# HEATER-SSR.net
KiCad netlist of a schematic drawn in Altium Designer
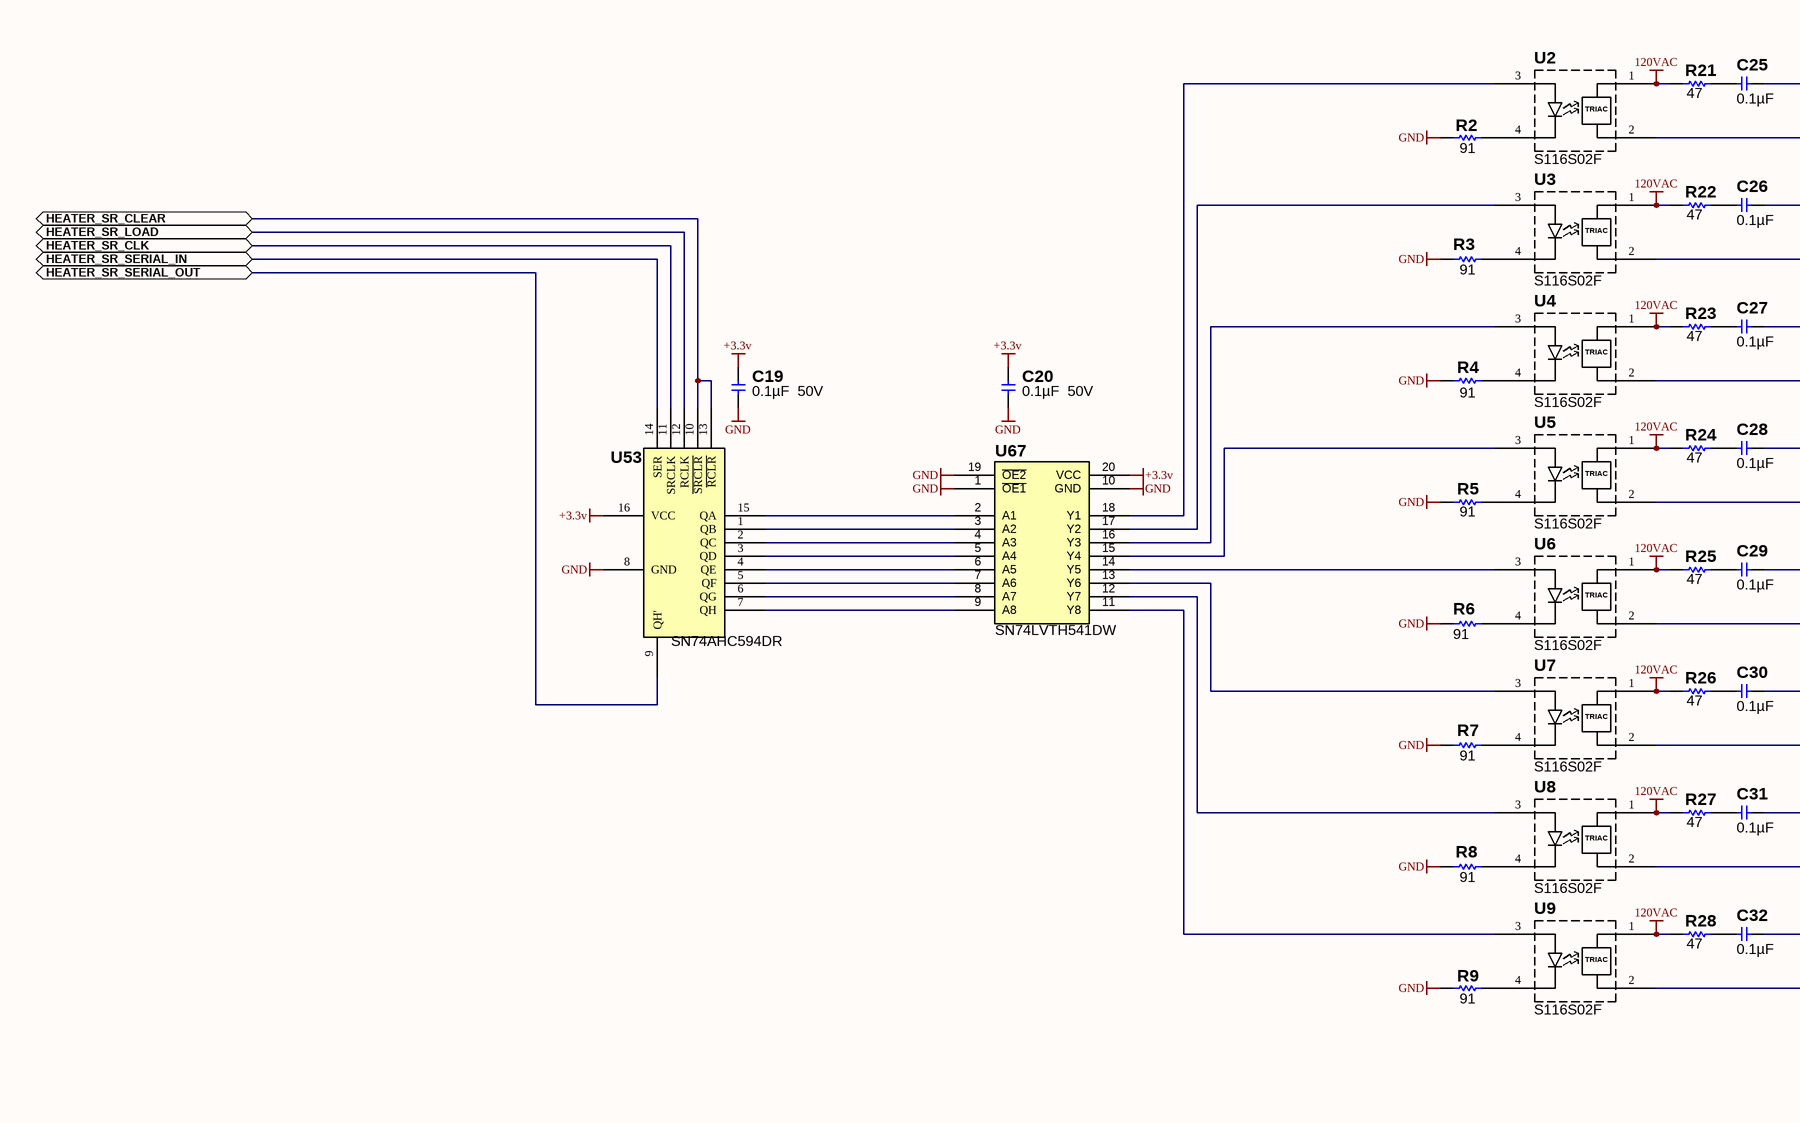
[diagram p0: HEATER-SSR.SchDoc, left]
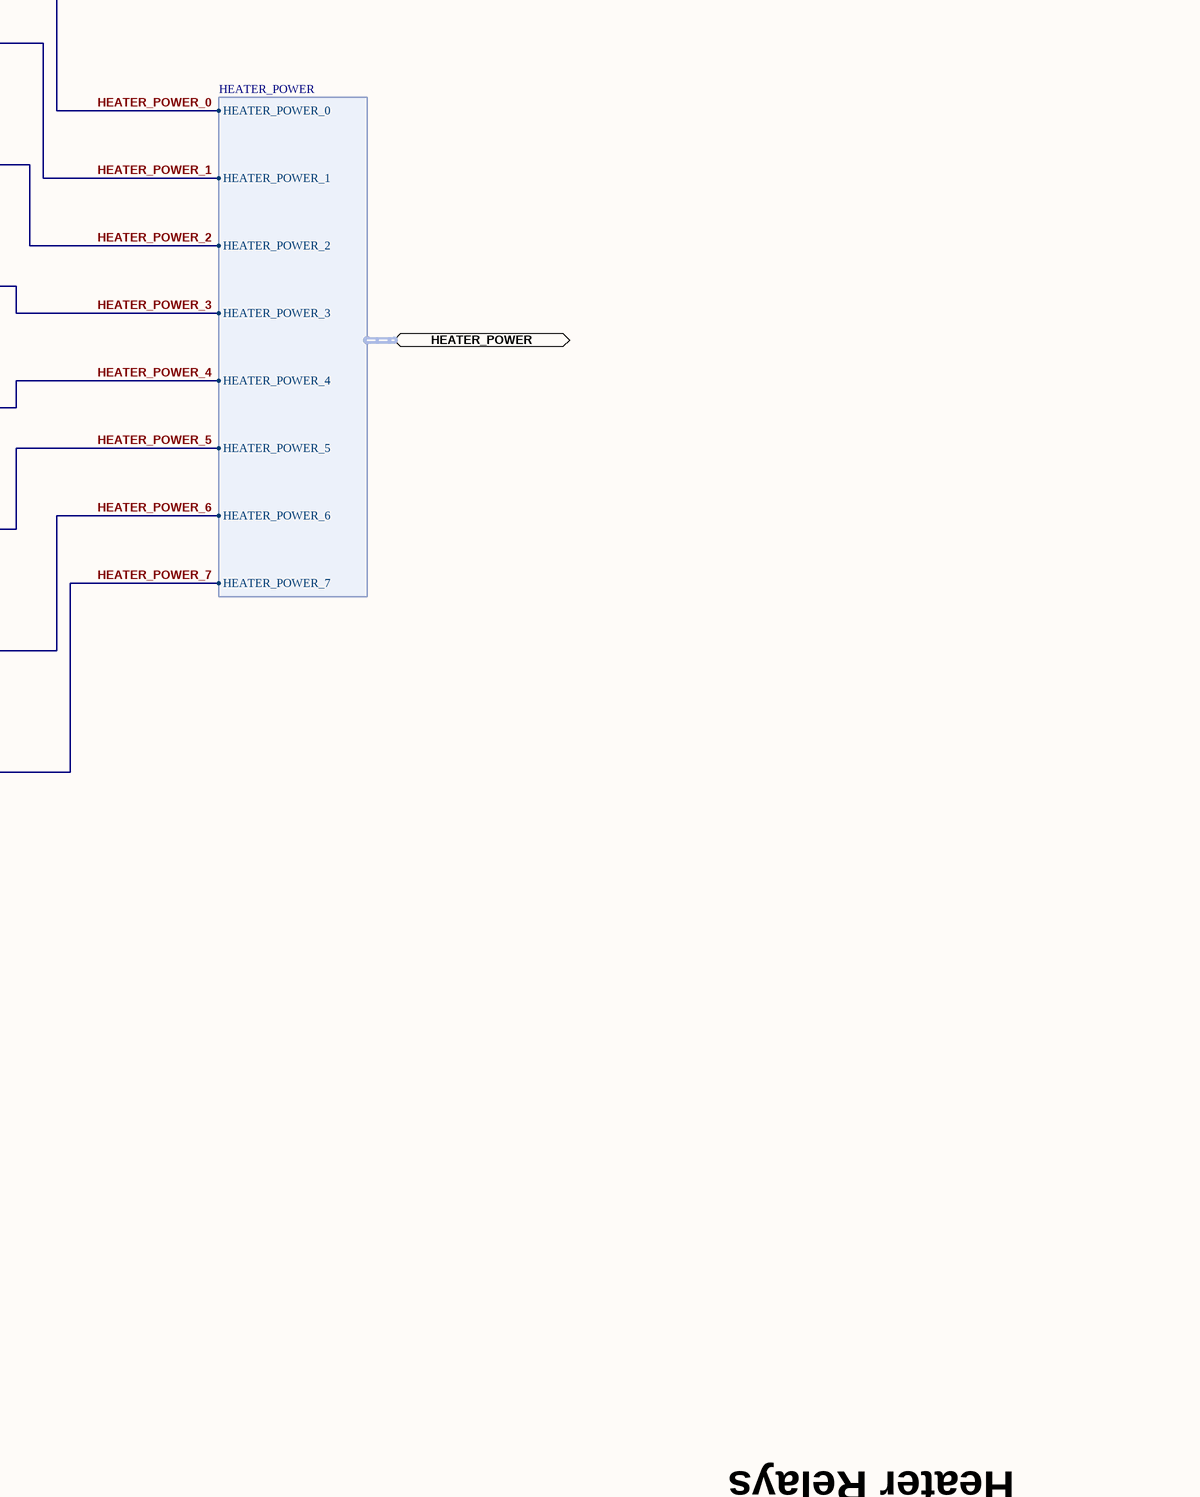
[diagram p1: HEATER-SSR.SchDoc, right]

(export (version "E")
  (design (tool "Eeschema 10.0.6"))
  (components
    (comp (ref "C19")
      (value "0.1µF  50V")
      (footprint "C0805_LD")
      (description "CAP CER 0.1UF 50V 10% X7R 0805")
      (fields
        (field (name "MANUFACTURER PART NUMBER") "GRM21BR71H104KA01L")
        (field (name "MANUFACTURER") "Murata Electronics North America")
      )
      (libsource (lib "Capacitors") (part "C_2P_NP"))
    )
    (comp (ref "C20")
      (value "0.1µF  50V")
      (footprint "C0805_LD")
      (description "CAP CER 0.1UF 50V 10% X7R 0805")
      (fields
        (field (name "MANUFACTURER PART NUMBER") "GRM21BR71H104KA01L")
        (field (name "MANUFACTURER") "Murata Electronics North America")
      )
      (libsource (lib "Capacitors") (part "C_2P_NP"))
    )
    (comp (ref "C25")
      (value "0.1µF")
      (footprint "C1206_LD")
      (description "CAP CER 0.1UF 250V 10% X7R 1206")
      (fields
        (field (name "MANUFACTURER PART NUMBER") "GRM31CR72E104KW03L")
        (field (name "MANUFACTURER") "Murata Electronics North America")
      )
      (libsource (lib "Diodes") (part "C_2P_NP"))
    )
    (comp (ref "C26")
      (value "0.1µF")
      (footprint "C1206_LD")
      (description "CAP CER 0.1UF 250V 10% X7R 1206")
      (fields
        (field (name "MANUFACTURER PART NUMBER") "GRM31CR72E104KW03L")
        (field (name "MANUFACTURER") "Murata Electronics North America")
      )
      (libsource (lib "Diodes") (part "C_2P_NP"))
    )
    (comp (ref "C27")
      (value "0.1µF")
      (footprint "C1206_LD")
      (description "CAP CER 0.1UF 250V 10% X7R 1206")
      (fields
        (field (name "MANUFACTURER PART NUMBER") "GRM31CR72E104KW03L")
        (field (name "MANUFACTURER") "Murata Electronics North America")
      )
      (libsource (lib "Diodes") (part "C_2P_NP"))
    )
    (comp (ref "C28")
      (value "0.1µF")
      (footprint "C1206_LD")
      (description "CAP CER 0.1UF 250V 10% X7R 1206")
      (fields
        (field (name "MANUFACTURER PART NUMBER") "GRM31CR72E104KW03L")
        (field (name "MANUFACTURER") "Murata Electronics North America")
      )
      (libsource (lib "Diodes") (part "C_2P_NP"))
    )
    (comp (ref "C29")
      (value "0.1µF")
      (footprint "C1206_LD")
      (description "CAP CER 0.1UF 250V 10% X7R 1206")
      (fields
        (field (name "MANUFACTURER PART NUMBER") "GRM31CR72E104KW03L")
        (field (name "MANUFACTURER") "Murata Electronics North America")
      )
      (libsource (lib "Diodes") (part "C_2P_NP"))
    )
    (comp (ref "C30")
      (value "0.1µF")
      (footprint "C1206_LD")
      (description "CAP CER 0.1UF 250V 10% X7R 1206")
      (fields
        (field (name "MANUFACTURER PART NUMBER") "GRM31CR72E104KW03L")
        (field (name "MANUFACTURER") "Murata Electronics North America")
      )
      (libsource (lib "Diodes") (part "C_2P_NP"))
    )
    (comp (ref "C31")
      (value "0.1µF")
      (footprint "C1206_LD")
      (description "CAP CER 0.1UF 250V 10% X7R 1206")
      (fields
        (field (name "MANUFACTURER PART NUMBER") "GRM31CR72E104KW03L")
        (field (name "MANUFACTURER") "Murata Electronics North America")
      )
      (libsource (lib "Diodes") (part "C_2P_NP"))
    )
    (comp (ref "C32")
      (value "0.1µF")
      (footprint "C1206_LD")
      (description "CAP CER 0.1UF 250V 10% X7R 1206")
      (fields
        (field (name "MANUFACTURER PART NUMBER") "GRM31CR72E104KW03L")
        (field (name "MANUFACTURER") "Murata Electronics North America")
      )
      (libsource (lib "Diodes") (part "C_2P_NP"))
    )
    (comp (ref "R2")
      (value "91")
      (footprint "R0805_LD")
      (description "RES 91 OHM 1/8W 1% 0805 SMD")
      (fields
        (field (name "MANUFACTURER PART NUMBER") "ERJ-6ENF91R0V")
        (field (name "MANUFACTURER") "Panasonic Electronic Components")
      )
      (libsource (lib "Resistors") (part "R_2P"))
    )
    (comp (ref "R3")
      (value "91")
      (footprint "R0805_LD")
      (description "RES 91 OHM 1/8W 1% 0805 SMD")
      (fields
        (field (name "MANUFACTURER PART NUMBER") "ERJ-6ENF91R0V")
        (field (name "MANUFACTURER") "Panasonic Electronic Components")
      )
      (libsource (lib "Resistors") (part "R_2P"))
    )
    (comp (ref "R4")
      (value "91")
      (footprint "R0805_LD")
      (description "RES 91 OHM 1/8W 1% 0805 SMD")
      (fields
        (field (name "MANUFACTURER PART NUMBER") "ERJ-6ENF91R0V")
        (field (name "MANUFACTURER") "Panasonic Electronic Components")
      )
      (libsource (lib "Resistors") (part "R_2P"))
    )
    (comp (ref "R5")
      (value "91")
      (footprint "R0805_LD")
      (description "RES 91 OHM 1/8W 1% 0805 SMD")
      (fields
        (field (name "MANUFACTURER PART NUMBER") "ERJ-6ENF91R0V")
        (field (name "MANUFACTURER") "Panasonic Electronic Components")
      )
      (libsource (lib "Resistors") (part "R_2P"))
    )
    (comp (ref "R6")
      (value "91")
      (footprint "R0805_LD")
      (description "RES 91 OHM 1/8W 1% 0805 SMD")
      (fields
        (field (name "MANUFACTURER PART NUMBER") "ERJ-6ENF91R0V")
        (field (name "MANUFACTURER") "Panasonic Electronic Components")
      )
      (libsource (lib "Resistors") (part "R_2P"))
    )
    (comp (ref "R7")
      (value "91")
      (footprint "R0805_LD")
      (description "RES 91 OHM 1/8W 1% 0805 SMD")
      (fields
        (field (name "MANUFACTURER PART NUMBER") "ERJ-6ENF91R0V")
        (field (name "MANUFACTURER") "Panasonic Electronic Components")
      )
      (libsource (lib "Resistors") (part "R_2P"))
    )
    (comp (ref "R8")
      (value "91")
      (footprint "R0805_LD")
      (description "RES 91 OHM 1/8W 1% 0805 SMD")
      (fields
        (field (name "MANUFACTURER PART NUMBER") "ERJ-6ENF91R0V")
        (field (name "MANUFACTURER") "Panasonic Electronic Components")
      )
      (libsource (lib "Resistors") (part "R_2P"))
    )
    (comp (ref "R9")
      (value "91")
      (footprint "R0805_LD")
      (description "RES 91 OHM 1/8W 1% 0805 SMD")
      (fields
        (field (name "MANUFACTURER PART NUMBER") "ERJ-6ENF91R0V")
        (field (name "MANUFACTURER") "Panasonic Electronic Components")
      )
      (libsource (lib "Resistors") (part "R_2P"))
    )
    (comp (ref "R21")
      (value "47")
      (footprint "R1206_LD")
      (description "RES 47 OHM 1/4W 1% 1206 SMD")
      (fields
        (field (name "MANUFACTURER PART NUMBER") "ERJ-8ENF47R0V")
        (field (name "MANUFACTURER") "Panasonic Electronic Components")
      )
      (libsource (lib "Diodes") (part "R_2P"))
    )
    (comp (ref "R22")
      (value "47")
      (footprint "R1206_LD")
      (description "RES 47 OHM 1/4W 1% 1206 SMD")
      (fields
        (field (name "MANUFACTURER PART NUMBER") "ERJ-8ENF47R0V")
        (field (name "MANUFACTURER") "Panasonic Electronic Components")
      )
      (libsource (lib "Diodes") (part "R_2P"))
    )
    (comp (ref "R23")
      (value "47")
      (footprint "R1206_LD")
      (description "RES 47 OHM 1/4W 1% 1206 SMD")
      (fields
        (field (name "MANUFACTURER PART NUMBER") "ERJ-8ENF47R0V")
        (field (name "MANUFACTURER") "Panasonic Electronic Components")
      )
      (libsource (lib "Diodes") (part "R_2P"))
    )
    (comp (ref "R24")
      (value "47")
      (footprint "R1206_LD")
      (description "RES 47 OHM 1/4W 1% 1206 SMD")
      (fields
        (field (name "MANUFACTURER PART NUMBER") "ERJ-8ENF47R0V")
        (field (name "MANUFACTURER") "Panasonic Electronic Components")
      )
      (libsource (lib "Diodes") (part "R_2P"))
    )
    (comp (ref "R25")
      (value "47")
      (footprint "R1206_LD")
      (description "RES 47 OHM 1/4W 1% 1206 SMD")
      (fields
        (field (name "MANUFACTURER PART NUMBER") "ERJ-8ENF47R0V")
        (field (name "MANUFACTURER") "Panasonic Electronic Components")
      )
      (libsource (lib "Diodes") (part "R_2P"))
    )
    (comp (ref "R26")
      (value "47")
      (footprint "R1206_LD")
      (description "RES 47 OHM 1/4W 1% 1206 SMD")
      (fields
        (field (name "MANUFACTURER PART NUMBER") "ERJ-8ENF47R0V")
        (field (name "MANUFACTURER") "Panasonic Electronic Components")
      )
      (libsource (lib "Diodes") (part "R_2P"))
    )
    (comp (ref "R27")
      (value "47")
      (footprint "R1206_LD")
      (description "RES 47 OHM 1/4W 1% 1206 SMD")
      (fields
        (field (name "MANUFACTURER PART NUMBER") "ERJ-8ENF47R0V")
        (field (name "MANUFACTURER") "Panasonic Electronic Components")
      )
      (libsource (lib "Diodes") (part "R_2P"))
    )
    (comp (ref "R28")
      (value "47")
      (footprint "R1206_LD")
      (description "RES 47 OHM 1/4W 1% 1206 SMD")
      (fields
        (field (name "MANUFACTURER PART NUMBER") "ERJ-8ENF47R0V")
        (field (name "MANUFACTURER") "Panasonic Electronic Components")
      )
      (libsource (lib "Diodes") (part "R_2P"))
    )
    (comp (ref "U2")
      (value "S116S02F")
      (footprint "SHARP SIP-4 SSR")
      (description "Solid State Relays - PCB Mount 16A Zero Cross Type Triac output SSR")
      (fields (field (name "MANUFACTURER") "Sharp Microelectronics"))
      (libsource (lib "eIC") (part "S116S02F"))
    )
    (comp (ref "U3")
      (value "S116S02F")
      (footprint "SHARP SIP-4 SSR")
      (description "Solid State Relays - PCB Mount 16A Zero Cross Type Triac output SSR")
      (fields (field (name "MANUFACTURER") "Sharp Microelectronics"))
      (libsource (lib "eIC") (part "S116S02F"))
    )
    (comp (ref "U4")
      (value "S116S02F")
      (footprint "SHARP SIP-4 SSR")
      (description "Solid State Relays - PCB Mount 16A Zero Cross Type Triac output SSR")
      (fields (field (name "MANUFACTURER") "Sharp Microelectronics"))
      (libsource (lib "eIC") (part "S116S02F"))
    )
    (comp (ref "U5")
      (value "S116S02F")
      (footprint "SHARP SIP-4 SSR")
      (description "Solid State Relays - PCB Mount 16A Zero Cross Type Triac output SSR")
      (fields (field (name "MANUFACTURER") "Sharp Microelectronics"))
      (libsource (lib "eIC") (part "S116S02F"))
    )
    (comp (ref "U6")
      (value "S116S02F")
      (footprint "SHARP SIP-4 SSR")
      (description "Solid State Relays - PCB Mount 16A Zero Cross Type Triac output SSR")
      (fields (field (name "MANUFACTURER") "Sharp Microelectronics"))
      (libsource (lib "eIC") (part "S116S02F"))
    )
    (comp (ref "U7")
      (value "S116S02F")
      (footprint "SHARP SIP-4 SSR")
      (description "Solid State Relays - PCB Mount 16A Zero Cross Type Triac output SSR")
      (fields (field (name "MANUFACTURER") "Sharp Microelectronics"))
      (libsource (lib "eIC") (part "S116S02F"))
    )
    (comp (ref "U8")
      (value "S116S02F")
      (footprint "SHARP SIP-4 SSR")
      (description "Solid State Relays - PCB Mount 16A Zero Cross Type Triac output SSR")
      (fields (field (name "MANUFACTURER") "Sharp Microelectronics"))
      (libsource (lib "eIC") (part "S116S02F"))
    )
    (comp (ref "U9")
      (value "S116S02F")
      (footprint "SHARP SIP-4 SSR")
      (description "Solid State Relays - PCB Mount 16A Zero Cross Type Triac output SSR")
      (fields (field (name "MANUFACTURER") "Sharp Microelectronics"))
      (libsource (lib "eIC") (part "S116S02F"))
    )
    (comp (ref "U53")
      (value "SN74AHC594DR")
      (footprint "SOIC127P600X145-16L")
      (description "IC SHIFT REGISTER 8BIT 16-SOIC")
      (fields (field (name "MANUFACTURER") "Texas Instruments"))
      (libsource (lib "eIC") (part "SN74AHC594DR"))
    )
    (comp (ref "U67")
      (value "SN74LVTH541DW")
      (footprint "SOIC127P1030X265-20L")
      (description "IC BUFF/DVR TRI-ST 8BIT 20SOIC")
      (fields (field (name "MANUFACTURER") "Texas Instruments"))
      (libsource (lib "eIC") (part "SN74LVTH541DW"))
    )
  )
  (nets
    (net (code "2") (name "+3.3v") (class "Default")
      (node (ref "C19") (pin "2") (pinfunction "2_2") (pintype "passive"))
      (node (ref "C20") (pin "2") (pinfunction "2_2") (pintype "passive"))
      (node (ref "U53") (pin "16") (pinfunction "VCC_16") (pintype "passive"))
      (node (ref "U67") (pin "20") (pinfunction "VCC_20") (pintype "passive"))
    )
    (net (code "3") (name "/HEATER_POWER_0") (class "Default")
      (node (ref "C25") (pin "2") (pinfunction "2_2") (pintype "passive"))
      (node (ref "U2") (pin "2") (pinfunction "2_2") (pintype "passive"))
    )
    (net (code "4") (name "/HEATER_POWER_1") (class "Default")
      (node (ref "C26") (pin "2") (pinfunction "2_2") (pintype "passive"))
      (node (ref "U3") (pin "2") (pinfunction "2_2") (pintype "passive"))
    )
    (net (code "5") (name "/HEATER_POWER_2") (class "Default")
      (node (ref "C27") (pin "2") (pinfunction "2_2") (pintype "passive"))
      (node (ref "U4") (pin "2") (pinfunction "2_2") (pintype "passive"))
    )
    (net (code "6") (name "/HEATER_POWER_3") (class "Default")
      (node (ref "C28") (pin "2") (pinfunction "2_2") (pintype "passive"))
      (node (ref "U5") (pin "2") (pinfunction "2_2") (pintype "passive"))
    )
    (net (code "7") (name "/HEATER_POWER_4") (class "Default")
      (node (ref "C29") (pin "2") (pinfunction "2_2") (pintype "passive"))
      (node (ref "U6") (pin "2") (pinfunction "2_2") (pintype "passive"))
    )
    (net (code "8") (name "/HEATER_POWER_5") (class "Default")
      (node (ref "C30") (pin "2") (pinfunction "2_2") (pintype "passive"))
      (node (ref "U7") (pin "2") (pinfunction "2_2") (pintype "passive"))
    )
    (net (code "9") (name "/HEATER_POWER_6") (class "Default")
      (node (ref "C31") (pin "2") (pinfunction "2_2") (pintype "passive"))
      (node (ref "U8") (pin "2") (pinfunction "2_2") (pintype "passive"))
    )
    (net (code "10") (name "/HEATER_POWER_7") (class "Default")
      (node (ref "C32") (pin "2") (pinfunction "2_2") (pintype "passive"))
      (node (ref "U9") (pin "2") (pinfunction "2_2") (pintype "passive"))
    )
    (net (code "11") (name "/HEATER_SR_CLEAR") (class "Default")
      (node (ref "U53") (pin "10") (pinfunction "~{SRCLR}_10") (pintype "passive"))
      (node (ref "U53") (pin "13") (pinfunction "~{RCLR}_13") (pintype "passive"))
    )
    (net (code "12") (name "/HEATER_SR_CLK") (class "Default")
      (node (ref "U53") (pin "11") (pinfunction "SRCLK_11") (pintype "passive"))
    )
    (net (code "13") (name "/HEATER_SR_LOAD") (class "Default")
      (node (ref "U53") (pin "12") (pinfunction "RCLK_12") (pintype "passive"))
    )
    (net (code "14") (name "/HEATER_SR_SERIAL_IN") (class "Default")
      (node (ref "U53") (pin "14") (pinfunction "SER_14") (pintype "passive"))
    )
    (net (code "15") (name "/HEATER_SR_SERIAL_OUT") (class "Default")
      (node (ref "U53") (pin "9") (pinfunction "QH'_9") (pintype "passive"))
    )
    (net (code "17") (name "120VAC") (class "Default")
      (node (ref "R21") (pin "1") (pinfunction "1_1") (pintype "passive"))
      (node (ref "R22") (pin "1") (pinfunction "1_1") (pintype "passive"))
      (node (ref "R23") (pin "1") (pinfunction "1_1") (pintype "passive"))
      (node (ref "R24") (pin "1") (pinfunction "1_1") (pintype "passive"))
      (node (ref "R25") (pin "1") (pinfunction "1_1") (pintype "passive"))
      (node (ref "R26") (pin "1") (pinfunction "1_1") (pintype "passive"))
      (node (ref "R27") (pin "1") (pinfunction "1_1") (pintype "passive"))
      (node (ref "R28") (pin "1") (pinfunction "1_1") (pintype "passive"))
      (node (ref "U2") (pin "1") (pinfunction "1_1") (pintype "passive"))
      (node (ref "U3") (pin "1") (pinfunction "1_1") (pintype "passive"))
      (node (ref "U4") (pin "1") (pinfunction "1_1") (pintype "passive"))
      (node (ref "U5") (pin "1") (pinfunction "1_1") (pintype "passive"))
      (node (ref "U6") (pin "1") (pinfunction "1_1") (pintype "passive"))
      (node (ref "U7") (pin "1") (pinfunction "1_1") (pintype "passive"))
      (node (ref "U8") (pin "1") (pinfunction "1_1") (pintype "passive"))
      (node (ref "U9") (pin "1") (pinfunction "1_1") (pintype "passive"))
    )
    (net (code "18") (name "GND") (class "Default")
      (node (ref "C19") (pin "1") (pinfunction "1_1") (pintype "passive"))
      (node (ref "C20") (pin "1") (pinfunction "1_1") (pintype "passive"))
      (node (ref "R2") (pin "1") (pinfunction "1_1") (pintype "passive"))
      (node (ref "R3") (pin "1") (pinfunction "1_1") (pintype "passive"))
      (node (ref "R4") (pin "1") (pinfunction "1_1") (pintype "passive"))
      (node (ref "R5") (pin "1") (pinfunction "1_1") (pintype "passive"))
      (node (ref "R6") (pin "1") (pinfunction "1_1") (pintype "passive"))
      (node (ref "R7") (pin "1") (pinfunction "1_1") (pintype "passive"))
      (node (ref "R8") (pin "1") (pinfunction "1_1") (pintype "passive"))
      (node (ref "R9") (pin "1") (pinfunction "1_1") (pintype "passive"))
      (node (ref "U53") (pin "8") (pinfunction "GND_8") (pintype "passive"))
      (node (ref "U67") (pin "1") (pinfunction "~{OE1}_1") (pintype "passive"))
      (node (ref "U67") (pin "10") (pinfunction "GND_10") (pintype "passive"))
      (node (ref "U67") (pin "19") (pinfunction "~{OE2}_19") (pintype "passive"))
    )
    (net (code "19") (name "Net-(C25-Pad1)") (class "Default")
      (node (ref "C25") (pin "1") (pinfunction "1_1") (pintype "passive"))
      (node (ref "R21") (pin "2") (pinfunction "2_2") (pintype "passive"))
    )
    (net (code "20") (name "Net-(C26-Pad1)") (class "Default")
      (node (ref "C26") (pin "1") (pinfunction "1_1") (pintype "passive"))
      (node (ref "R22") (pin "2") (pinfunction "2_2") (pintype "passive"))
    )
    (net (code "21") (name "Net-(C27-Pad1)") (class "Default")
      (node (ref "C27") (pin "1") (pinfunction "1_1") (pintype "passive"))
      (node (ref "R23") (pin "2") (pinfunction "2_2") (pintype "passive"))
    )
    (net (code "22") (name "Net-(C28-Pad1)") (class "Default")
      (node (ref "C28") (pin "1") (pinfunction "1_1") (pintype "passive"))
      (node (ref "R24") (pin "2") (pinfunction "2_2") (pintype "passive"))
    )
    (net (code "23") (name "Net-(C29-Pad1)") (class "Default")
      (node (ref "C29") (pin "1") (pinfunction "1_1") (pintype "passive"))
      (node (ref "R25") (pin "2") (pinfunction "2_2") (pintype "passive"))
    )
    (net (code "24") (name "Net-(C30-Pad1)") (class "Default")
      (node (ref "C30") (pin "1") (pinfunction "1_1") (pintype "passive"))
      (node (ref "R26") (pin "2") (pinfunction "2_2") (pintype "passive"))
    )
    (net (code "25") (name "Net-(C31-Pad1)") (class "Default")
      (node (ref "C31") (pin "1") (pinfunction "1_1") (pintype "passive"))
      (node (ref "R27") (pin "2") (pinfunction "2_2") (pintype "passive"))
    )
    (net (code "26") (name "Net-(C32-Pad1)") (class "Default")
      (node (ref "C32") (pin "1") (pinfunction "1_1") (pintype "passive"))
      (node (ref "R28") (pin "2") (pinfunction "2_2") (pintype "passive"))
    )
    (net (code "27") (name "Net-(R2-Pad2)") (class "Default")
      (node (ref "R2") (pin "2") (pinfunction "2_2") (pintype "passive"))
      (node (ref "U2") (pin "4") (pinfunction "4_4") (pintype "passive"))
    )
    (net (code "28") (name "Net-(R3-Pad2)") (class "Default")
      (node (ref "R3") (pin "2") (pinfunction "2_2") (pintype "passive"))
      (node (ref "U3") (pin "4") (pinfunction "4_4") (pintype "passive"))
    )
    (net (code "29") (name "Net-(R4-Pad2)") (class "Default")
      (node (ref "R4") (pin "2") (pinfunction "2_2") (pintype "passive"))
      (node (ref "U4") (pin "4") (pinfunction "4_4") (pintype "passive"))
    )
    (net (code "30") (name "Net-(R5-Pad2)") (class "Default")
      (node (ref "R5") (pin "2") (pinfunction "2_2") (pintype "passive"))
      (node (ref "U5") (pin "4") (pinfunction "4_4") (pintype "passive"))
    )
    (net (code "31") (name "Net-(R6-Pad2)") (class "Default")
      (node (ref "R6") (pin "2") (pinfunction "2_2") (pintype "passive"))
      (node (ref "U6") (pin "4") (pinfunction "4_4") (pintype "passive"))
    )
    (net (code "32") (name "Net-(R7-Pad2)") (class "Default")
      (node (ref "R7") (pin "2") (pinfunction "2_2") (pintype "passive"))
      (node (ref "U7") (pin "4") (pinfunction "4_4") (pintype "passive"))
    )
    (net (code "33") (name "Net-(R8-Pad2)") (class "Default")
      (node (ref "R8") (pin "2") (pinfunction "2_2") (pintype "passive"))
      (node (ref "U8") (pin "4") (pinfunction "4_4") (pintype "passive"))
    )
    (net (code "34") (name "Net-(R9-Pad2)") (class "Default")
      (node (ref "R9") (pin "2") (pinfunction "2_2") (pintype "passive"))
      (node (ref "U9") (pin "4") (pinfunction "4_4") (pintype "passive"))
    )
    (net (code "35") (name "Net-(U53-QA)") (class "Default")
      (node (ref "U53") (pin "15") (pinfunction "QA_15") (pintype "passive"))
      (node (ref "U67") (pin "2") (pinfunction "A1_2") (pintype "passive"))
    )
    (net (code "36") (name "Net-(U53-QB)") (class "Default")
      (node (ref "U53") (pin "1") (pinfunction "QB_1") (pintype "passive"))
      (node (ref "U67") (pin "3") (pinfunction "A2_3") (pintype "passive"))
    )
    (net (code "37") (name "Net-(U53-QC)") (class "Default")
      (node (ref "U53") (pin "2") (pinfunction "QC_2") (pintype "passive"))
      (node (ref "U67") (pin "4") (pinfunction "A3_4") (pintype "passive"))
    )
    (net (code "38") (name "Net-(U53-QD)") (class "Default")
      (node (ref "U53") (pin "3") (pinfunction "QD_3") (pintype "passive"))
      (node (ref "U67") (pin "5") (pinfunction "A4_5") (pintype "passive"))
    )
    (net (code "39") (name "Net-(U53-QE)") (class "Default")
      (node (ref "U53") (pin "4") (pinfunction "QE_4") (pintype "passive"))
      (node (ref "U67") (pin "6") (pinfunction "A5_6") (pintype "passive"))
    )
    (net (code "40") (name "Net-(U53-QF)") (class "Default")
      (node (ref "U53") (pin "5") (pinfunction "QF_5") (pintype "passive"))
      (node (ref "U67") (pin "7") (pinfunction "A6_7") (pintype "passive"))
    )
    (net (code "41") (name "Net-(U53-QG)") (class "Default")
      (node (ref "U53") (pin "6") (pinfunction "QG_6") (pintype "passive"))
      (node (ref "U67") (pin "8") (pinfunction "A7_8") (pintype "passive"))
    )
    (net (code "42") (name "Net-(U53-QH)") (class "Default")
      (node (ref "U53") (pin "7") (pinfunction "QH_7") (pintype "passive"))
      (node (ref "U67") (pin "9") (pinfunction "A8_9") (pintype "passive"))
    )
    (net (code "43") (name "Net-(U67-Y1)") (class "Default")
      (node (ref "U2") (pin "3") (pinfunction "3_3") (pintype "passive"))
      (node (ref "U67") (pin "18") (pinfunction "Y1_18") (pintype "passive"))
    )
    (net (code "44") (name "Net-(U67-Y2)") (class "Default")
      (node (ref "U3") (pin "3") (pinfunction "3_3") (pintype "passive"))
      (node (ref "U67") (pin "17") (pinfunction "Y2_17") (pintype "passive"))
    )
    (net (code "45") (name "Net-(U67-Y3)") (class "Default")
      (node (ref "U4") (pin "3") (pinfunction "3_3") (pintype "passive"))
      (node (ref "U67") (pin "16") (pinfunction "Y3_16") (pintype "passive"))
    )
    (net (code "46") (name "Net-(U67-Y4)") (class "Default")
      (node (ref "U5") (pin "3") (pinfunction "3_3") (pintype "passive"))
      (node (ref "U67") (pin "15") (pinfunction "Y4_15") (pintype "passive"))
    )
    (net (code "47") (name "Net-(U67-Y5)") (class "Default")
      (node (ref "U6") (pin "3") (pinfunction "3_3") (pintype "passive"))
      (node (ref "U67") (pin "14") (pinfunction "Y5_14") (pintype "passive"))
    )
    (net (code "48") (name "Net-(U67-Y6)") (class "Default")
      (node (ref "U67") (pin "13") (pinfunction "Y6_13") (pintype "passive"))
      (node (ref "U7") (pin "3") (pinfunction "3_3") (pintype "passive"))
    )
    (net (code "49") (name "Net-(U67-Y7)") (class "Default")
      (node (ref "U67") (pin "12") (pinfunction "Y7_12") (pintype "passive"))
      (node (ref "U8") (pin "3") (pinfunction "3_3") (pintype "passive"))
    )
    (net (code "50") (name "Net-(U67-Y8)") (class "Default")
      (node (ref "U67") (pin "11") (pinfunction "Y8_11") (pintype "passive"))
      (node (ref "U9") (pin "3") (pinfunction "3_3") (pintype "passive"))
    )
  )
)
